# CRAFT_E_Stop_AJeffersonRev2.net
KiCad netlist of a schematic drawn in Altium Designer
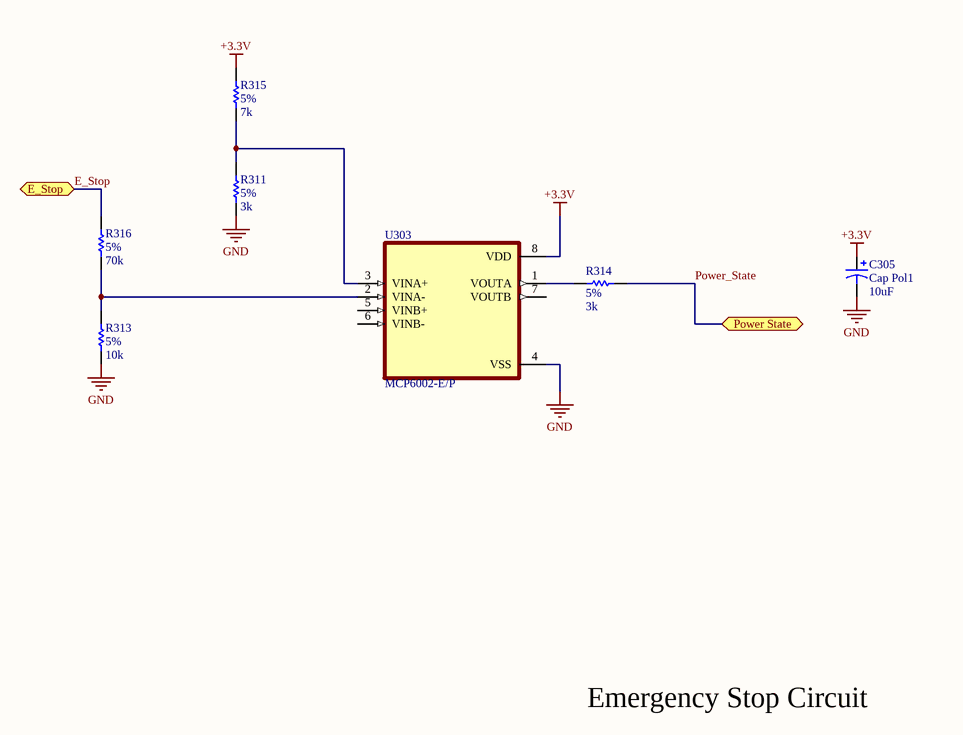
[diagram p0: CRAFT_E_Stop_AJeffersonRev2.SchDoc]

(export (version "E")
  (design (tool "Eeschema 10.0.6"))
  (components
    (comp (ref "C305")
      (value "Cap Pol1")
      (footprint "CAPPRD250W50D630H1120")
      (description "Polarized Capacitor (Radial)")
      (fields (field (name "ALTIUM_VALUE") "10uF") (field (name "PUBLISHER") "Altium Limited"))
      (libsource (lib "Miscellaneous Devices") (part "Cap Pol1"))
    )
    (comp (ref "R311")
      (value "5%")
      (footprint "AXIAL-0.3")
      (description "Resistor")
      (fields (field (name "ALTIUM_VALUE") "3k") (field (name "PUBLISHER") "Altium Limited"))
      (libsource (lib "Miscellaneous Devices") (part "Res1"))
    )
    (comp (ref "R313")
      (value "5%")
      (footprint "AXIAL-0.3")
      (description "Resistor")
      (fields (field (name "ALTIUM_VALUE") "10k") (field (name "PUBLISHER") "Altium Limited"))
      (libsource (lib "Miscellaneous Devices") (part "Res1"))
    )
    (comp (ref "R314")
      (value "5%")
      (footprint "AXIAL-0.3")
      (description "Resistor")
      (fields (field (name "ALTIUM_VALUE") "3k") (field (name "PUBLISHER") "Altium Limited"))
      (libsource (lib "Miscellaneous Devices") (part "Res1"))
    )
    (comp (ref "R315")
      (value "5%")
      (footprint "AXIAL-0.3")
      (description "Resistor")
      (fields (field (name "ALTIUM_VALUE") "7k") (field (name "PUBLISHER") "Altium Limited"))
      (libsource (lib "Miscellaneous Devices") (part "Res1"))
    )
    (comp (ref "R316")
      (value "5%")
      (footprint "AXIAL-0.3")
      (description "Resistor")
      (fields (field (name "ALTIUM_VALUE") "70k") (field (name "PUBLISHER") "Altium Limited"))
      (libsource (lib "Miscellaneous Devices") (part "Res1"))
    )
    (comp (ref "U303")
      (value "MCP6002-E/P")
      (footprint "DIP787W46P254L927H533Q8")
      (description "General Purpose Amplifier 2 Circuit Rail-to-Rail 8-PDIP")
      (fields (field (name "MF") "Microchip"))
      (libsource (lib "MCP6002-E_P") (part "MCP6002-E/P"))
    )
  )
  (nets
    (net (code "1") (name "+3.3V") (class "Default")
      (node (ref "C305") (pin "1") (pinfunction "1_1") (pintype "passive"))
      (node (ref "R315") (pin "2") (pinfunction "2_2") (pintype "passive"))
      (node (ref "U303") (pin "8") (pinfunction "VDD_8") (pintype "power_in"))
    )
    (net (code "2") (name "/E_Stop") (class "Default")
      (node (ref "R316") (pin "2") (pinfunction "2_2") (pintype "passive"))
    )
    (net (code "3") (name "/Power_State") (class "Default")
      (node (ref "R314") (pin "2") (pinfunction "2_2") (pintype "passive"))
    )
    (net (code "4") (name "GND") (class "Default")
      (node (ref "C305") (pin "2") (pinfunction "2_2") (pintype "passive"))
      (node (ref "R311") (pin "1") (pinfunction "1_1") (pintype "passive"))
      (node (ref "R313") (pin "1") (pinfunction "1_1") (pintype "passive"))
      (node (ref "U303") (pin "4") (pinfunction "VSS_4") (pintype "power_in"))
    )
    (net (code "5") (name "Net-(U303-VINA+)") (class "Default")
      (node (ref "R311") (pin "2") (pinfunction "2_2") (pintype "passive"))
      (node (ref "R315") (pin "1") (pinfunction "1_1") (pintype "passive"))
      (node (ref "U303") (pin "3") (pinfunction "VINA+_3") (pintype "input"))
    )
    (net (code "6") (name "Net-(U303-VINA-)") (class "Default")
      (node (ref "R313") (pin "2") (pinfunction "2_2") (pintype "passive"))
      (node (ref "R316") (pin "1") (pinfunction "1_1") (pintype "passive"))
      (node (ref "U303") (pin "2") (pinfunction "VINA-_2") (pintype "input"))
    )
    (net (code "7") (name "Net-(U303-VOUTA)") (class "Default")
      (node (ref "R314") (pin "1") (pinfunction "1_1") (pintype "passive"))
      (node (ref "U303") (pin "1") (pinfunction "VOUTA_1") (pintype "output"))
    )
    (net (code "8") (name "unconnected-(U303-VINB+-Pad5)") (class "Default")
      (node (ref "U303") (pin "5") (pinfunction "VINB+_5") (pintype "input"))
    )
    (net (code "9") (name "unconnected-(U303-VINB--Pad6)") (class "Default")
      (node (ref "U303") (pin "6") (pinfunction "VINB-_6") (pintype "input"))
    )
    (net (code "10") (name "unconnected-(U303-VOUTB-Pad7)") (class "Default")
      (node (ref "U303") (pin "7") (pinfunction "VOUTB_7") (pintype "output"))
    )
  )
)
